# Copernicus-DIP-Breakout.net
KiCad netlist of a schematic drawn in EAGLE
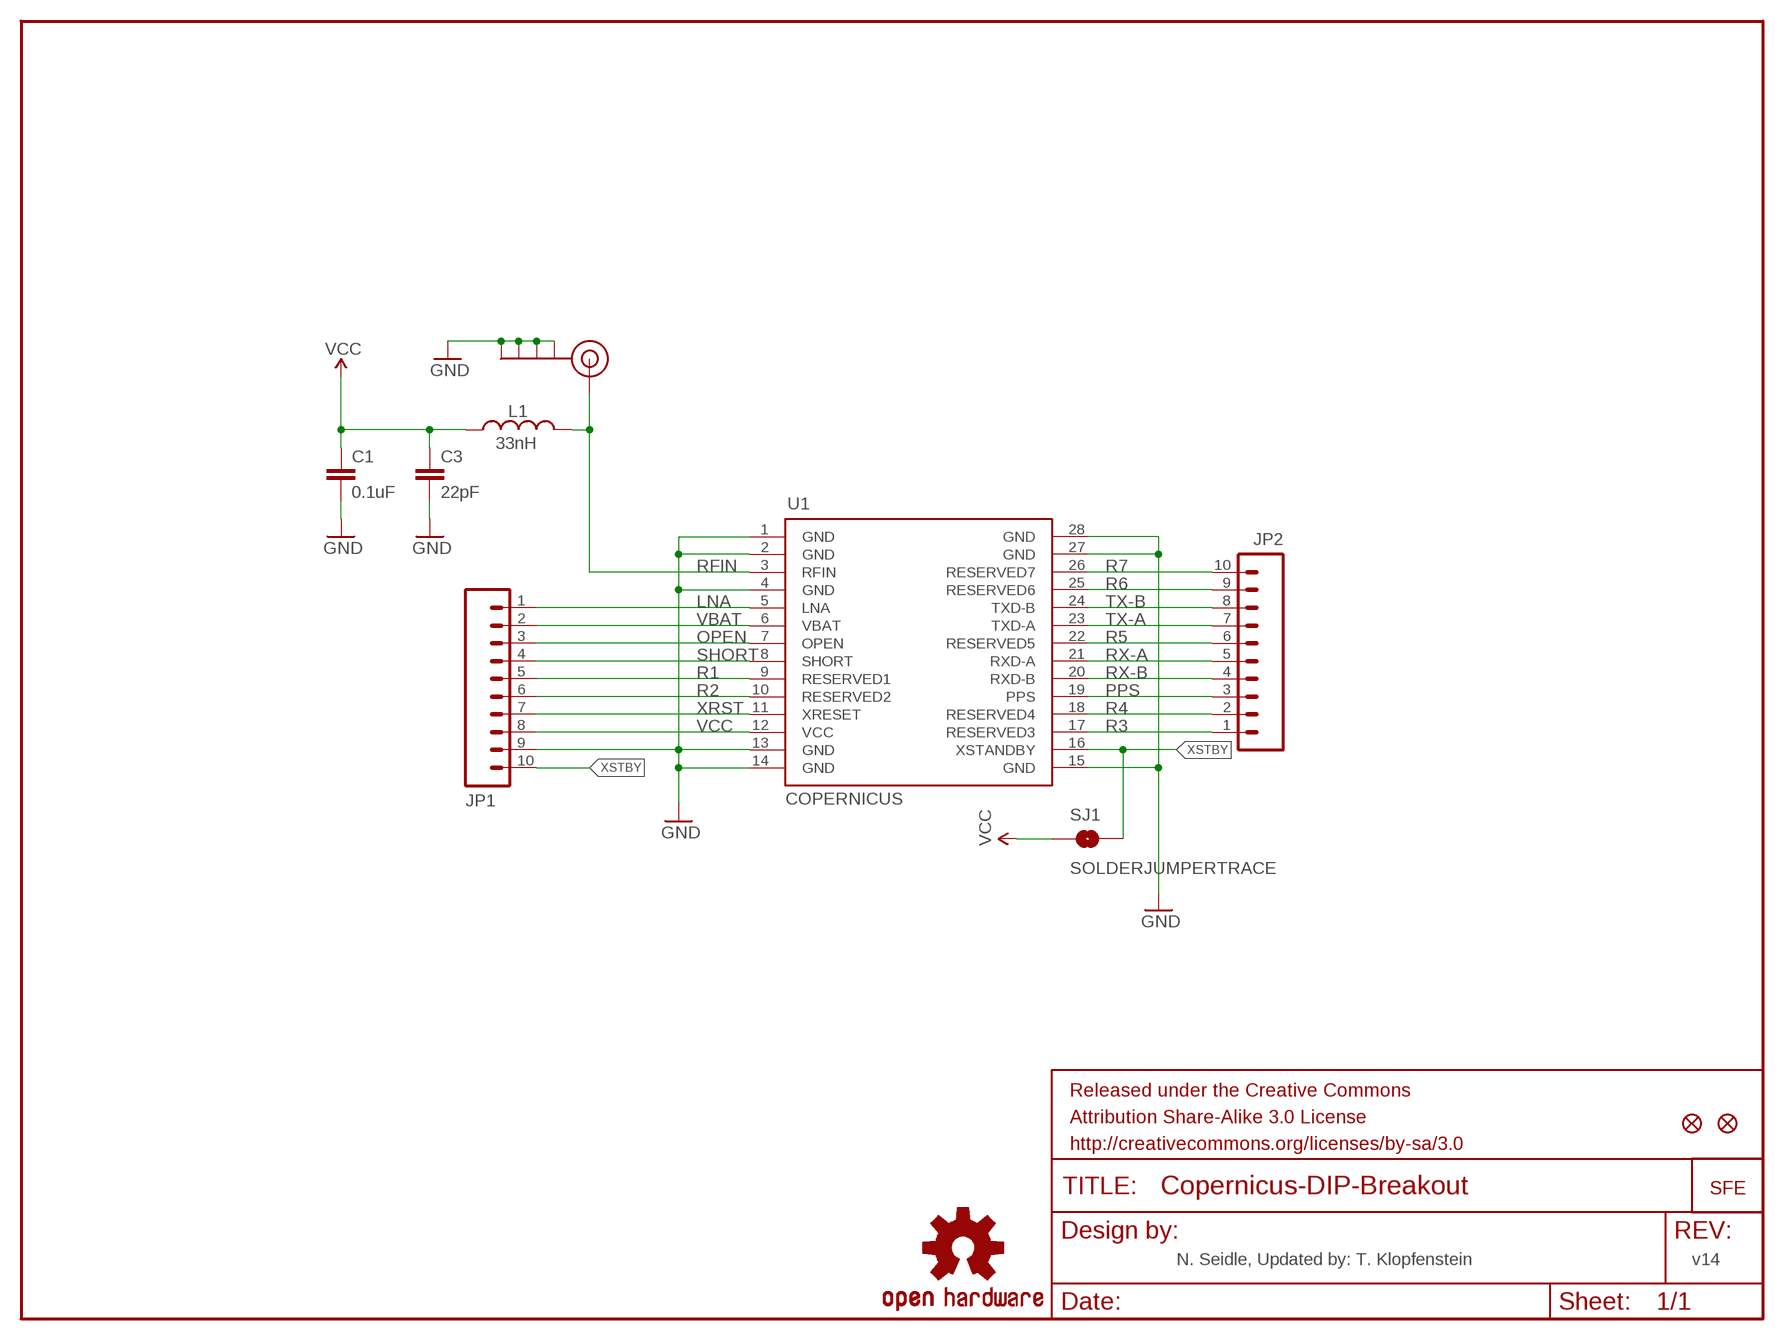
[diagram p0: schematic, sheet 1]

(export (version "E")
  (design (tool "Eeschema 10.0.6"))
  (components
    (comp (ref "C1")
      (value "0.1uF")
      (footprint "eagle-import:0603-CAP")
      (libsource (lib "eagle-import") (part "CAP0603-CAP"))
    )
    (comp (ref "C3")
      (value "22pF")
      (footprint "eagle-import:0603-CAP")
      (libsource (lib "eagle-import") (part "CAP0603-CAP"))
    )
    (comp (ref "FRAME1")
      (value "FRAME-LETTER")
      (footprint "eagle-import:CREATIVE_COMMONS")
      (libsource (lib "eagle-import") (part "FRAME-LETTER"))
    )
    (comp (ref "JP1")
      (value "M10\"")
      (footprint "eagle-import:1X10")
      (libsource (lib "eagle-import") (part "M10{dblquote}"))
    )
    (comp (ref "JP2")
      (value "M10\"")
      (footprint "eagle-import:1X10")
      (libsource (lib "eagle-import") (part "M10{dblquote}"))
    )
    (comp (ref "JP3")
      (value "SMA_EDGE")
      (footprint "eagle-import:SMA_EDGE")
      (libsource (lib "eagle-import") (part "SMA_EDGE"))
    )
    (comp (ref "JP4")
      (value "LOGO-SFESK")
      (footprint "eagle-import:SFE-LOGO-FLAME")
      (libsource (lib "eagle-import") (part "LOGO-SFESK"))
    )
    (comp (ref "L1")
      (value "33nH")
      (footprint "eagle-import:0603")
      (libsource (lib "eagle-import") (part "INDUCTOR0603"))
    )
    (comp (ref "SJ1")
      (value "SOLDERJUMPERTRACE")
      (footprint "eagle-import:SJ_2S-TRACE")
      (libsource (lib "eagle-import") (part "SOLDERJUMPERTRACE"))
    )
    (comp (ref "U$1")
      (value "OSHW-LOGOS")
      (footprint "eagle-import:OSHW-LOGO-S")
      (libsource (lib "eagle-import") (part "OSHW-LOGOS"))
    )
    (comp (ref "U$2")
      (value "FIDUCIAL1X2")
      (footprint "eagle-import:FIDUCIAL-1X2")
      (libsource (lib "eagle-import") (part "FIDUCIAL1X2"))
    )
    (comp (ref "U$3")
      (value "FIDUCIAL1X2")
      (footprint "eagle-import:FIDUCIAL-1X2")
      (libsource (lib "eagle-import") (part "FIDUCIAL1X2"))
    )
    (comp (ref "U1")
      (value "COPERNICUS")
      (footprint "eagle-import:COPERNICUS")
      (libsource (lib "eagle-import") (part "COPERNICUSSMD"))
    )
  )
  (nets
    (net (code "1") (name "/LNA") (class "Default")
      (node (ref "JP1") (pin "1") (pinfunction "1_1") (pintype "passive"))
      (node (ref "U1") (pin "5") (pinfunction "LNA_5") (pintype "bidirectional"))
    )
    (net (code "2") (name "/OPEN") (class "Default")
      (node (ref "JP1") (pin "3") (pinfunction "3_3") (pintype "passive"))
      (node (ref "U1") (pin "7") (pinfunction "OPEN_7") (pintype "bidirectional"))
    )
    (net (code "3") (name "/PPS") (class "Default")
      (node (ref "JP2") (pin "3") (pinfunction "3_3") (pintype "passive"))
      (node (ref "U1") (pin "19") (pinfunction "PPS_19") (pintype "bidirectional"))
    )
    (net (code "4") (name "/R1") (class "Default")
      (node (ref "JP1") (pin "5") (pinfunction "5_5") (pintype "passive"))
      (node (ref "U1") (pin "9") (pinfunction "RESERVED1_9") (pintype "bidirectional"))
    )
    (net (code "5") (name "/R2") (class "Default")
      (node (ref "JP1") (pin "6") (pinfunction "6_6") (pintype "passive"))
      (node (ref "U1") (pin "10") (pinfunction "RESERVED2_10") (pintype "bidirectional"))
    )
    (net (code "6") (name "/R3") (class "Default")
      (node (ref "JP2") (pin "1") (pinfunction "1_1") (pintype "passive"))
      (node (ref "U1") (pin "17") (pinfunction "RESERVED3_17") (pintype "bidirectional"))
    )
    (net (code "7") (name "/R4") (class "Default")
      (node (ref "JP2") (pin "2") (pinfunction "2_2") (pintype "passive"))
      (node (ref "U1") (pin "18") (pinfunction "RESERVED4_18") (pintype "bidirectional"))
    )
    (net (code "8") (name "/R5") (class "Default")
      (node (ref "JP2") (pin "6") (pinfunction "6_6") (pintype "passive"))
      (node (ref "U1") (pin "22") (pinfunction "RESERVED5_22") (pintype "bidirectional"))
    )
    (net (code "9") (name "/R6") (class "Default")
      (node (ref "JP2") (pin "9") (pinfunction "9_9") (pintype "passive"))
      (node (ref "U1") (pin "25") (pinfunction "RESERVED6_25") (pintype "bidirectional"))
    )
    (net (code "10") (name "/R7") (class "Default")
      (node (ref "JP2") (pin "10") (pinfunction "10_10") (pintype "passive"))
      (node (ref "U1") (pin "26") (pinfunction "RESERVED7_26") (pintype "bidirectional"))
    )
    (net (code "11") (name "/RFIN") (class "Default")
      (node (ref "JP3") (pin "SIG") (pinfunction "SIGNAL_SIG") (pintype "bidirectional"))
      (node (ref "L1") (pin "2") (pinfunction "2_2") (pintype "passive"))
      (node (ref "U1") (pin "3") (pinfunction "RFIN_3") (pintype "bidirectional"))
    )
    (net (code "12") (name "/RX-A") (class "Default")
      (node (ref "JP2") (pin "5") (pinfunction "5_5") (pintype "passive"))
      (node (ref "U1") (pin "21") (pinfunction "RXD-A_21") (pintype "bidirectional"))
    )
    (net (code "13") (name "/RX-B") (class "Default")
      (node (ref "JP2") (pin "4") (pinfunction "4_4") (pintype "passive"))
      (node (ref "U1") (pin "20") (pinfunction "RXD-B_20") (pintype "bidirectional"))
    )
    (net (code "14") (name "/SHORT") (class "Default")
      (node (ref "JP1") (pin "4") (pinfunction "4_4") (pintype "passive"))
      (node (ref "U1") (pin "8") (pinfunction "SHORT_8") (pintype "bidirectional"))
    )
    (net (code "15") (name "/TX-A") (class "Default")
      (node (ref "JP2") (pin "7") (pinfunction "7_7") (pintype "passive"))
      (node (ref "U1") (pin "23") (pinfunction "TXD-A_23") (pintype "bidirectional"))
    )
    (net (code "16") (name "/TX-B") (class "Default")
      (node (ref "JP2") (pin "8") (pinfunction "8_8") (pintype "passive"))
      (node (ref "U1") (pin "24") (pinfunction "TXD-B_24") (pintype "bidirectional"))
    )
    (net (code "17") (name "/VBAT") (class "Default")
      (node (ref "JP1") (pin "2") (pinfunction "2_2") (pintype "passive"))
      (node (ref "U1") (pin "6") (pinfunction "VBAT_6") (pintype "bidirectional"))
    )
    (net (code "18") (name "/XRST") (class "Default")
      (node (ref "JP1") (pin "7") (pinfunction "7_7") (pintype "passive"))
      (node (ref "U1") (pin "11") (pinfunction "XRESET_11") (pintype "bidirectional"))
    )
    (net (code "19") (name "GND") (class "Default")
      (node (ref "C1") (pin "2") (pinfunction "2_2") (pintype "passive"))
      (node (ref "C3") (pin "2") (pinfunction "2_2") (pintype "passive"))
      (node (ref "JP1") (pin "9") (pinfunction "9_9") (pintype "passive"))
      (node (ref "JP3") (pin "GND@0") (pinfunction "GND_GND@0") (pintype "bidirectional"))
      (node (ref "JP3") (pin "GND@1") (pinfunction "GND_GND@1") (pintype "bidirectional"))
      (node (ref "JP3") (pin "GND@2") (pinfunction "GND_GND@2") (pintype "bidirectional"))
      (node (ref "JP3") (pin "GND@3") (pinfunction "GND_GND@3") (pintype "bidirectional"))
      (node (ref "U1") (pin "1") (pinfunction "GND_1") (pintype "bidirectional"))
      (node (ref "U1") (pin "13") (pinfunction "GND_13") (pintype "bidirectional"))
      (node (ref "U1") (pin "14") (pinfunction "GND_14") (pintype "bidirectional"))
      (node (ref "U1") (pin "15") (pinfunction "GND_15") (pintype "bidirectional"))
      (node (ref "U1") (pin "2") (pinfunction "GND_2") (pintype "bidirectional"))
      (node (ref "U1") (pin "27") (pinfunction "GND_27") (pintype "bidirectional"))
      (node (ref "U1") (pin "28") (pinfunction "GND_28") (pintype "bidirectional"))
      (node (ref "U1") (pin "4") (pinfunction "GND_4") (pintype "bidirectional"))
    )
    (net (code "20") (name "VCC") (class "Default")
      (node (ref "C1") (pin "1") (pinfunction "1_1") (pintype "passive"))
      (node (ref "C3") (pin "1") (pinfunction "1_1") (pintype "passive"))
      (node (ref "JP1") (pin "8") (pinfunction "8_8") (pintype "passive"))
      (node (ref "L1") (pin "1") (pinfunction "1_1") (pintype "passive"))
      (node (ref "SJ1") (pin "1") (pinfunction "1_1") (pintype "passive"))
      (node (ref "U1") (pin "12") (pinfunction "VCC_12") (pintype "bidirectional"))
    )
    (net (code "21") (name "XSTBY") (class "Default")
      (node (ref "JP1") (pin "10") (pinfunction "10_10") (pintype "passive"))
      (node (ref "SJ1") (pin "2") (pinfunction "2_2") (pintype "passive"))
      (node (ref "U1") (pin "16") (pinfunction "XSTANDBY_16") (pintype "bidirectional"))
    )
  )
)
